# sensor_v3b.net
KiCad netlist of a schematic drawn in EAGLE
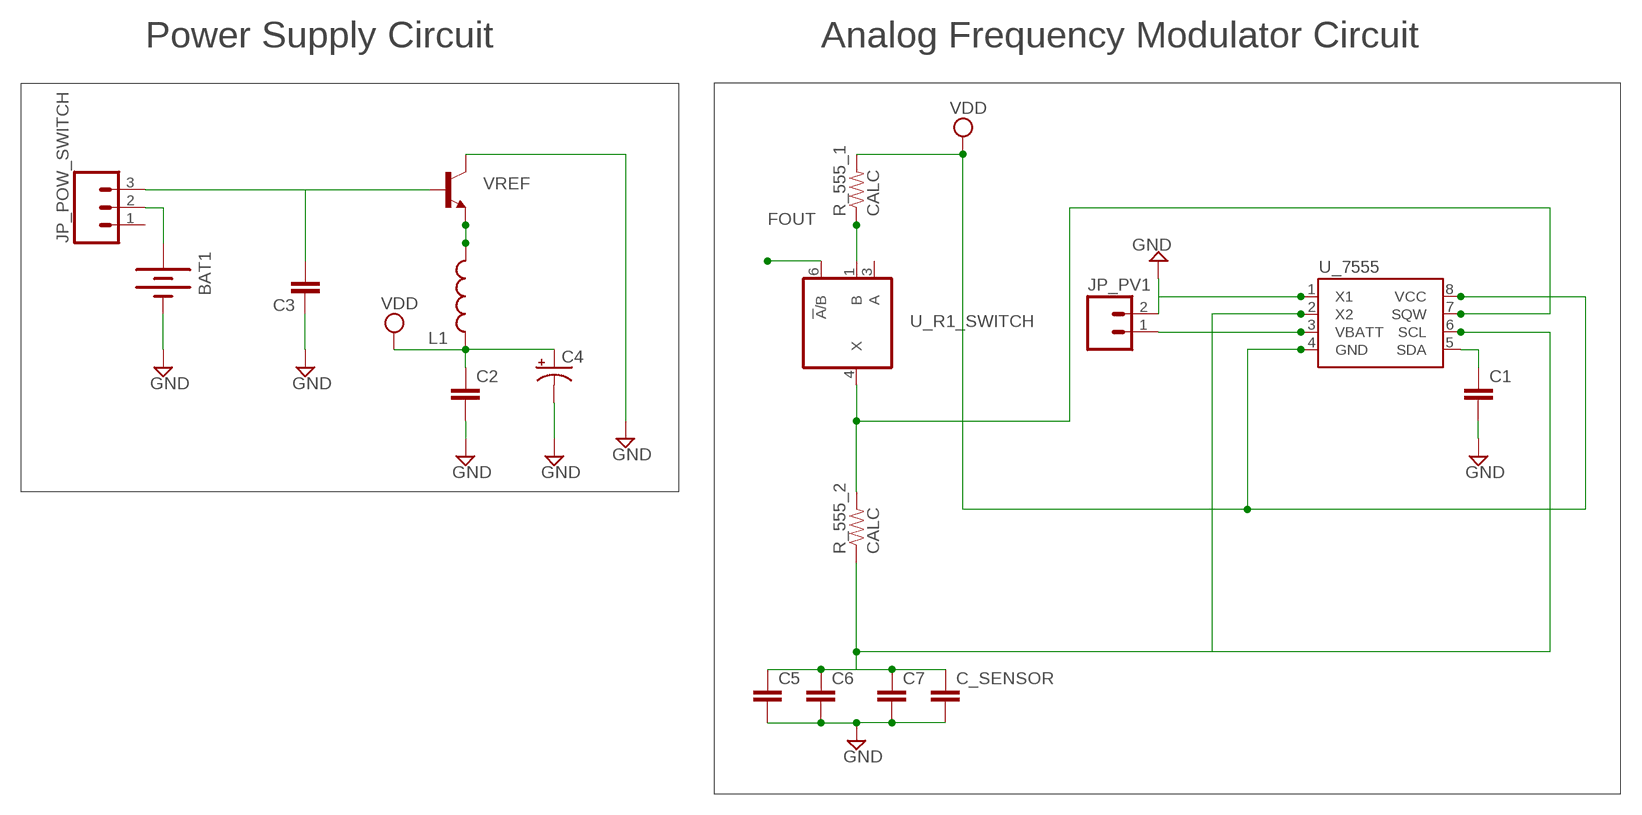
[diagram p0: schematic, sheet 1]

(export (version "E")
  (design (tool "Eeschema 10.0.6"))
  (components
    (comp (ref "BAT1")
      (value "BATTERY20PTH_LAB")
      (footprint "eagle-import:BATTCOM_20MM_PTH")
      (libsource (lib "eagle-import") (part "BATTERY20PTH_LAB"))
    )
    (comp (ref "C1")
      (value "CAP0603-CAP")
      (footprint "eagle-import:0603-CAP")
      (libsource (lib "eagle-import") (part "SparkFun-Capacitors_CAP0603-CAP"))
    )
    (comp (ref "C2")
      (value "CAP0603-CAP")
      (footprint "eagle-import:0603-CAP")
      (libsource (lib "eagle-import") (part "SparkFun-Capacitors_CAP0603-CAP"))
    )
    (comp (ref "C3")
      (value "CAP0603-CAP")
      (footprint "eagle-import:0603-CAP")
      (libsource (lib "eagle-import") (part "SparkFun-Capacitors_CAP0603-CAP"))
    )
    (comp (ref "C4")
      (value "CAP_POL1206")
      (footprint "eagle-import:EIA3216")
      (libsource (lib "eagle-import") (part "CAP_POL1206"))
    )
    (comp (ref "C5")
      (value "CAP0805")
      (footprint "eagle-import:0805")
      (libsource (lib "eagle-import") (part "CAP0805"))
    )
    (comp (ref "C6")
      (value "CAP0805")
      (footprint "eagle-import:0805")
      (libsource (lib "eagle-import") (part "CAP0805"))
    )
    (comp (ref "C7")
      (value "CAP0805")
      (footprint "eagle-import:0805")
      (libsource (lib "eagle-import") (part "CAP0805"))
    )
    (comp (ref "C_SENSOR")
      (value "CAP0805")
      (footprint "eagle-import:0805")
      (libsource (lib "eagle-import") (part "CAP0805"))
    )
    (comp (ref "JP_POW_SWITCH")
      (value "M03LOCK")
      (footprint "eagle-import:1X03_LOCK")
      (libsource (lib "eagle-import") (part "M03LOCK"))
    )
    (comp (ref "JP_PV1")
      (value "M02LOCK")
      (footprint "eagle-import:1X02_LOCK")
      (libsource (lib "eagle-import") (part "M02LOCK"))
    )
    (comp (ref "L1")
      (value "INDUCTOR0603")
      (footprint "eagle-import:0603")
      (libsource (lib "eagle-import") (part "INDUCTOR0603"))
    )
    (comp (ref "R_555_1")
      (value "CALC")
      (footprint "eagle-import:0805")
      (libsource (lib "eagle-import") (part "RESISTOR0805-RES"))
    )
    (comp (ref "R_555_2")
      (value "CALC")
      (footprint "eagle-import:0805")
      (libsource (lib "eagle-import") (part "RESISTOR0805-RES"))
    )
    (comp (ref "U_7555")
      (value "DS1307SO8")
      (footprint "eagle-import:SO08")
      (libsource (lib "eagle-import") (part "DS1307SO8"))
    )
    (comp (ref "U_R1_SWITCH")
      (value "741G3157DCKR")
      (footprint "eagle-import:DCK_R-PDSO-G6")
      (libsource (lib "eagle-import") (part "741G3157DCKR"))
    )
    (comp (ref "U_VREF")
      (value "TRANSISTOR_NPNSOT23-3")
      (footprint "eagle-import:SOT23-3")
      (libsource (lib "eagle-import") (part "TRANSISTOR_NPNSOT23-3"))
    )
  )
  (nets
    (net (code "1") (name "/FOUT") (class "Default")
      (node (ref "JP_PV1") (pin "1") (pinfunction "1_1") (pintype "passive"))
      (node (ref "U_7555") (pin "3") (pinfunction "VBATT_3") (pintype "bidirectional"))
      (node (ref "U_R1_SWITCH") (pin "6") (pinfunction "~{A}/B_6") (pintype "input"))
    )
    (net (code "2") (name "/P2") (class "Default")
      (node (ref "C5") (pin "1") (pinfunction "1_1") (pintype "passive"))
      (node (ref "C6") (pin "1") (pinfunction "1_1") (pintype "passive"))
      (node (ref "C7") (pin "1") (pinfunction "1_1") (pintype "passive"))
      (node (ref "C_SENSOR") (pin "1") (pinfunction "1_1") (pintype "passive"))
      (node (ref "R_555_2") (pin "1") (pinfunction "1_1") (pintype "passive"))
      (node (ref "U_7555") (pin "2") (pinfunction "X2_2") (pintype "bidirectional"))
      (node (ref "U_7555") (pin "6") (pinfunction "SCL_6") (pintype "bidirectional"))
    )
    (net (code "3") (name "GND") (class "Default")
      (node (ref "BAT1") (pin "2") (pinfunction "-_2") (pintype "power_in"))
      (node (ref "C1") (pin "2") (pinfunction "2_2") (pintype "passive"))
      (node (ref "C2") (pin "2") (pinfunction "2_2") (pintype "passive"))
      (node (ref "C3") (pin "1") (pinfunction "1_1") (pintype "passive"))
      (node (ref "C4") (pin "C") (pinfunction "-_C") (pintype "passive"))
      (node (ref "C5") (pin "2") (pinfunction "2_2") (pintype "passive"))
      (node (ref "C6") (pin "2") (pinfunction "2_2") (pintype "passive"))
      (node (ref "C7") (pin "2") (pinfunction "2_2") (pintype "passive"))
      (node (ref "C_SENSOR") (pin "2") (pinfunction "2_2") (pintype "passive"))
      (node (ref "JP_PV1") (pin "2") (pinfunction "2_2") (pintype "passive"))
      (node (ref "U_7555") (pin "1") (pinfunction "X1_1") (pintype "bidirectional"))
      (node (ref "U_VREF") (pin "3") (pinfunction "C_3") (pintype "passive"))
    )
    (net (code "4") (name "Net-(BAT1-+)") (class "Default")
      (node (ref "BAT1") (pin "1") (pinfunction "+_1") (pintype "power_in"))
      (node (ref "JP_POW_SWITCH") (pin "2") (pinfunction "2_2") (pintype "passive"))
    )
    (net (code "5") (name "Net-(U_7555-SDA)") (class "Default")
      (node (ref "C1") (pin "1") (pinfunction "1_1") (pintype "passive"))
      (node (ref "U_7555") (pin "5") (pinfunction "SDA_5") (pintype "bidirectional"))
    )
    (net (code "6") (name "Net-(U_7555-SQW)") (class "Default")
      (node (ref "R_555_2") (pin "2") (pinfunction "2_2") (pintype "passive"))
      (node (ref "U_7555") (pin "7") (pinfunction "SQW_7") (pintype "bidirectional"))
      (node (ref "U_R1_SWITCH") (pin "4") (pinfunction "X_4") (pintype "bidirectional"))
    )
    (net (code "7") (name "Net-(U_R1_SWITCHA-B)") (class "Default")
      (node (ref "R_555_1") (pin "1") (pinfunction "1_1") (pintype "passive"))
      (node (ref "U_R1_SWITCH") (pin "1") (pinfunction "B_1") (pintype "bidirectional"))
    )
    (net (code "8") (name "Net-(U_VREF-B)") (class "Default")
      (node (ref "C3") (pin "2") (pinfunction "2_2") (pintype "passive"))
      (node (ref "JP_POW_SWITCH") (pin "3") (pinfunction "3_3") (pintype "passive"))
      (node (ref "U_VREF") (pin "1") (pinfunction "B_1") (pintype "passive"))
    )
    (net (code "9") (name "Net-(U_VREF-E)") (class "Default")
      (node (ref "L1") (pin "2") (pinfunction "2_2") (pintype "passive"))
      (node (ref "U_VREF") (pin "2") (pinfunction "E_2") (pintype "passive"))
    )
    (net (code "10") (name "VDD") (class "Default")
      (node (ref "C2") (pin "1") (pinfunction "1_1") (pintype "passive"))
      (node (ref "C4") (pin "A") (pinfunction "+_A") (pintype "passive"))
      (node (ref "L1") (pin "1") (pinfunction "1_1") (pintype "passive"))
      (node (ref "R_555_1") (pin "2") (pinfunction "2_2") (pintype "passive"))
      (node (ref "U_7555") (pin "4") (pinfunction "GND_4") (pintype "bidirectional"))
      (node (ref "U_7555") (pin "8") (pinfunction "VCC_8") (pintype "bidirectional"))
    )
    (net (code "11") (name "unconnected-(JP_POW_SWITCH-Pad1)") (class "Default")
      (node (ref "JP_POW_SWITCH") (pin "1") (pinfunction "1_1") (pintype "passive"))
    )
    (net (code "12") (name "unconnected-(U_R1_SWITCHA-A-Pad3)") (class "Default")
      (node (ref "U_R1_SWITCH") (pin "3") (pinfunction "A_3") (pintype "bidirectional"))
    )
  )
)
